# Grove_-_ADC_for_load_cell_HX711.net
KiCad netlist of a schematic drawn in EAGLE
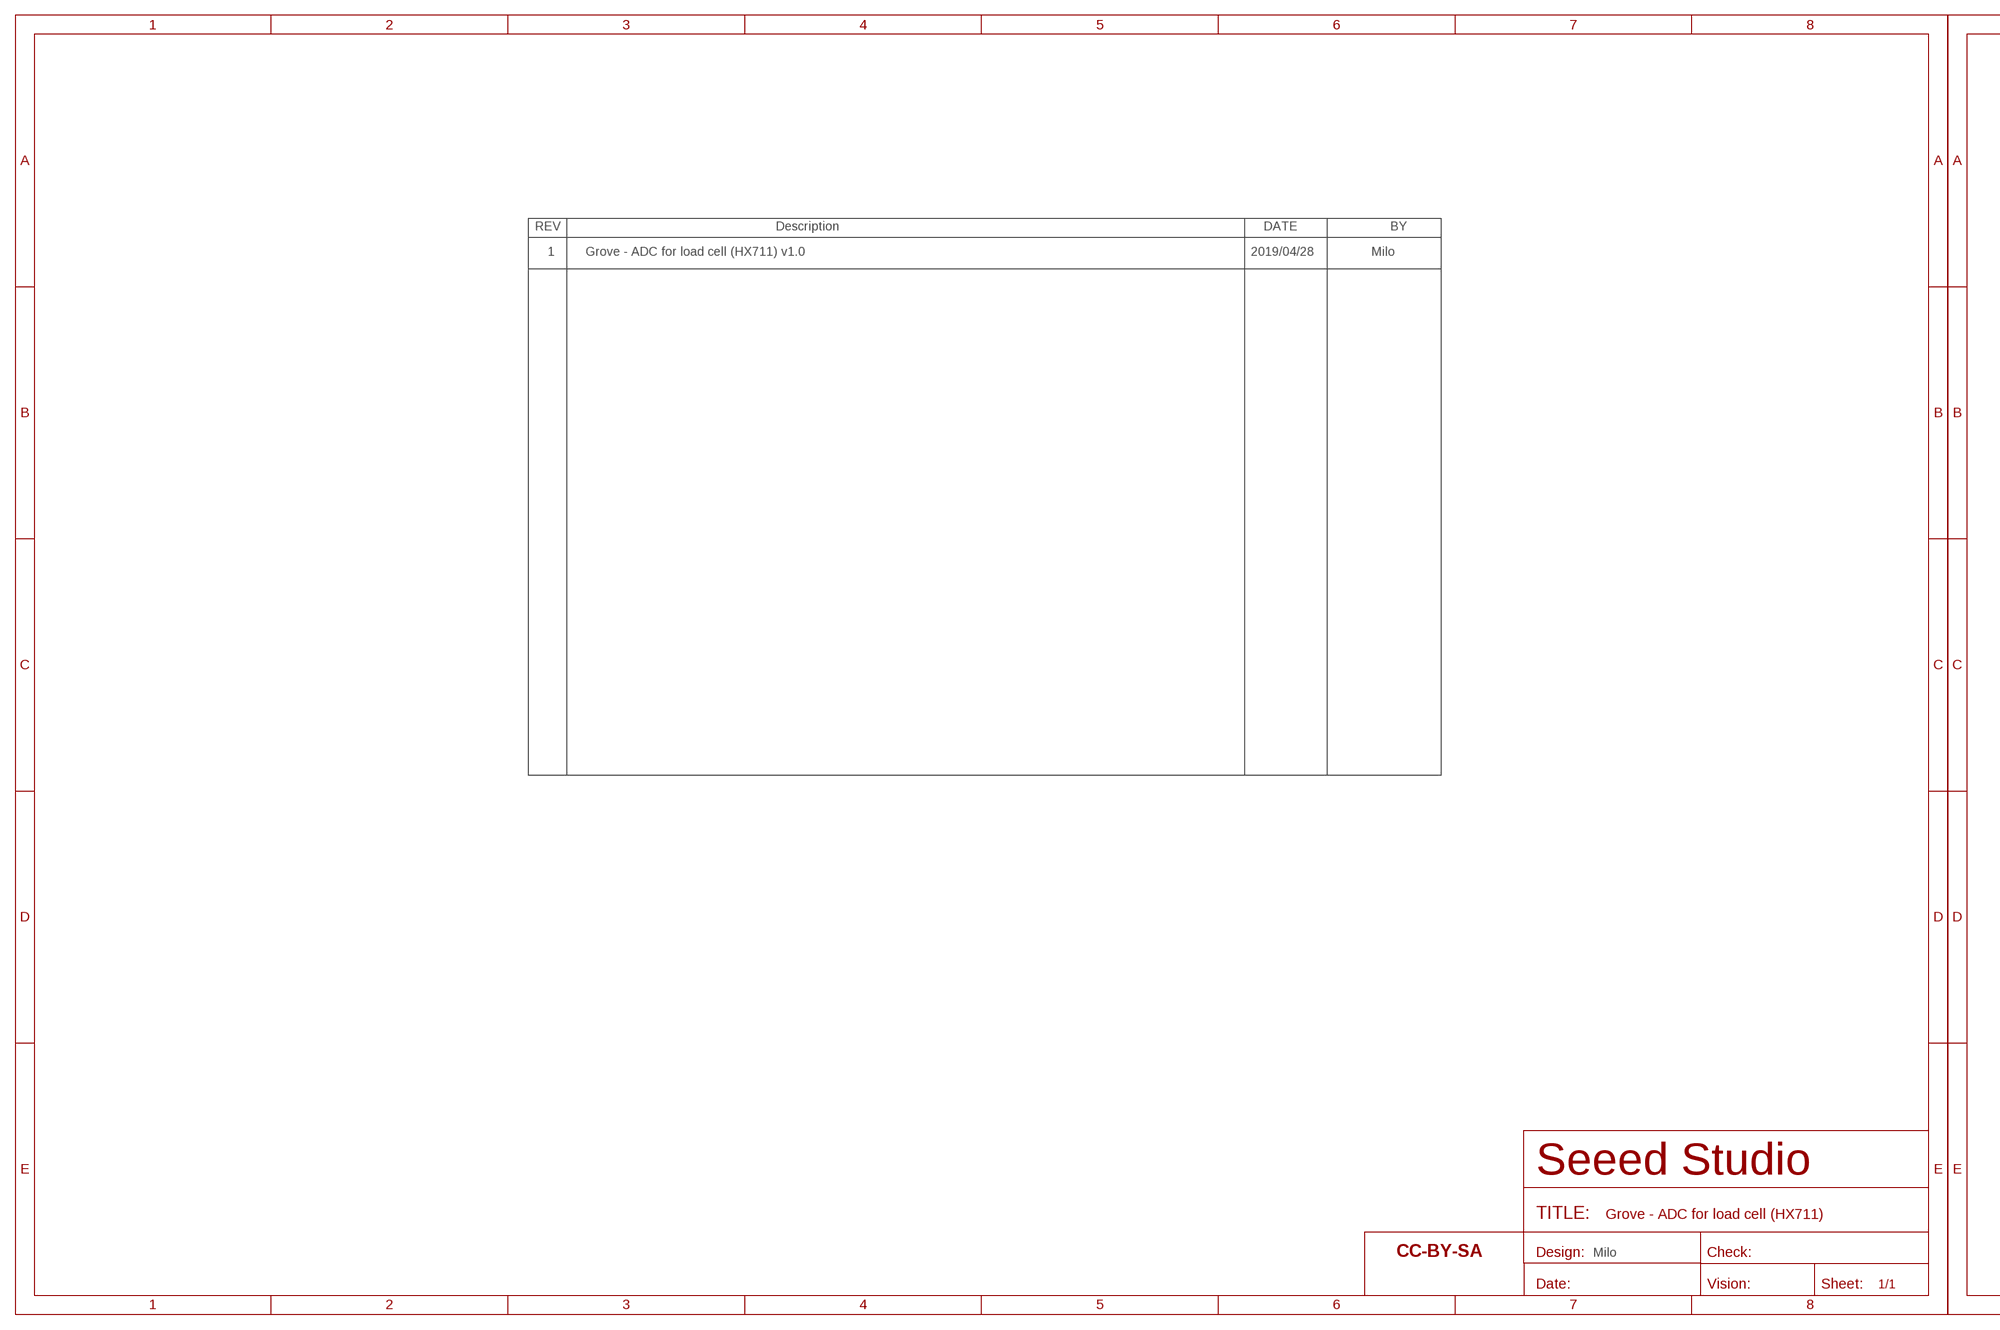
[diagram p0: schematic, sheet 1, part 1 of 2]
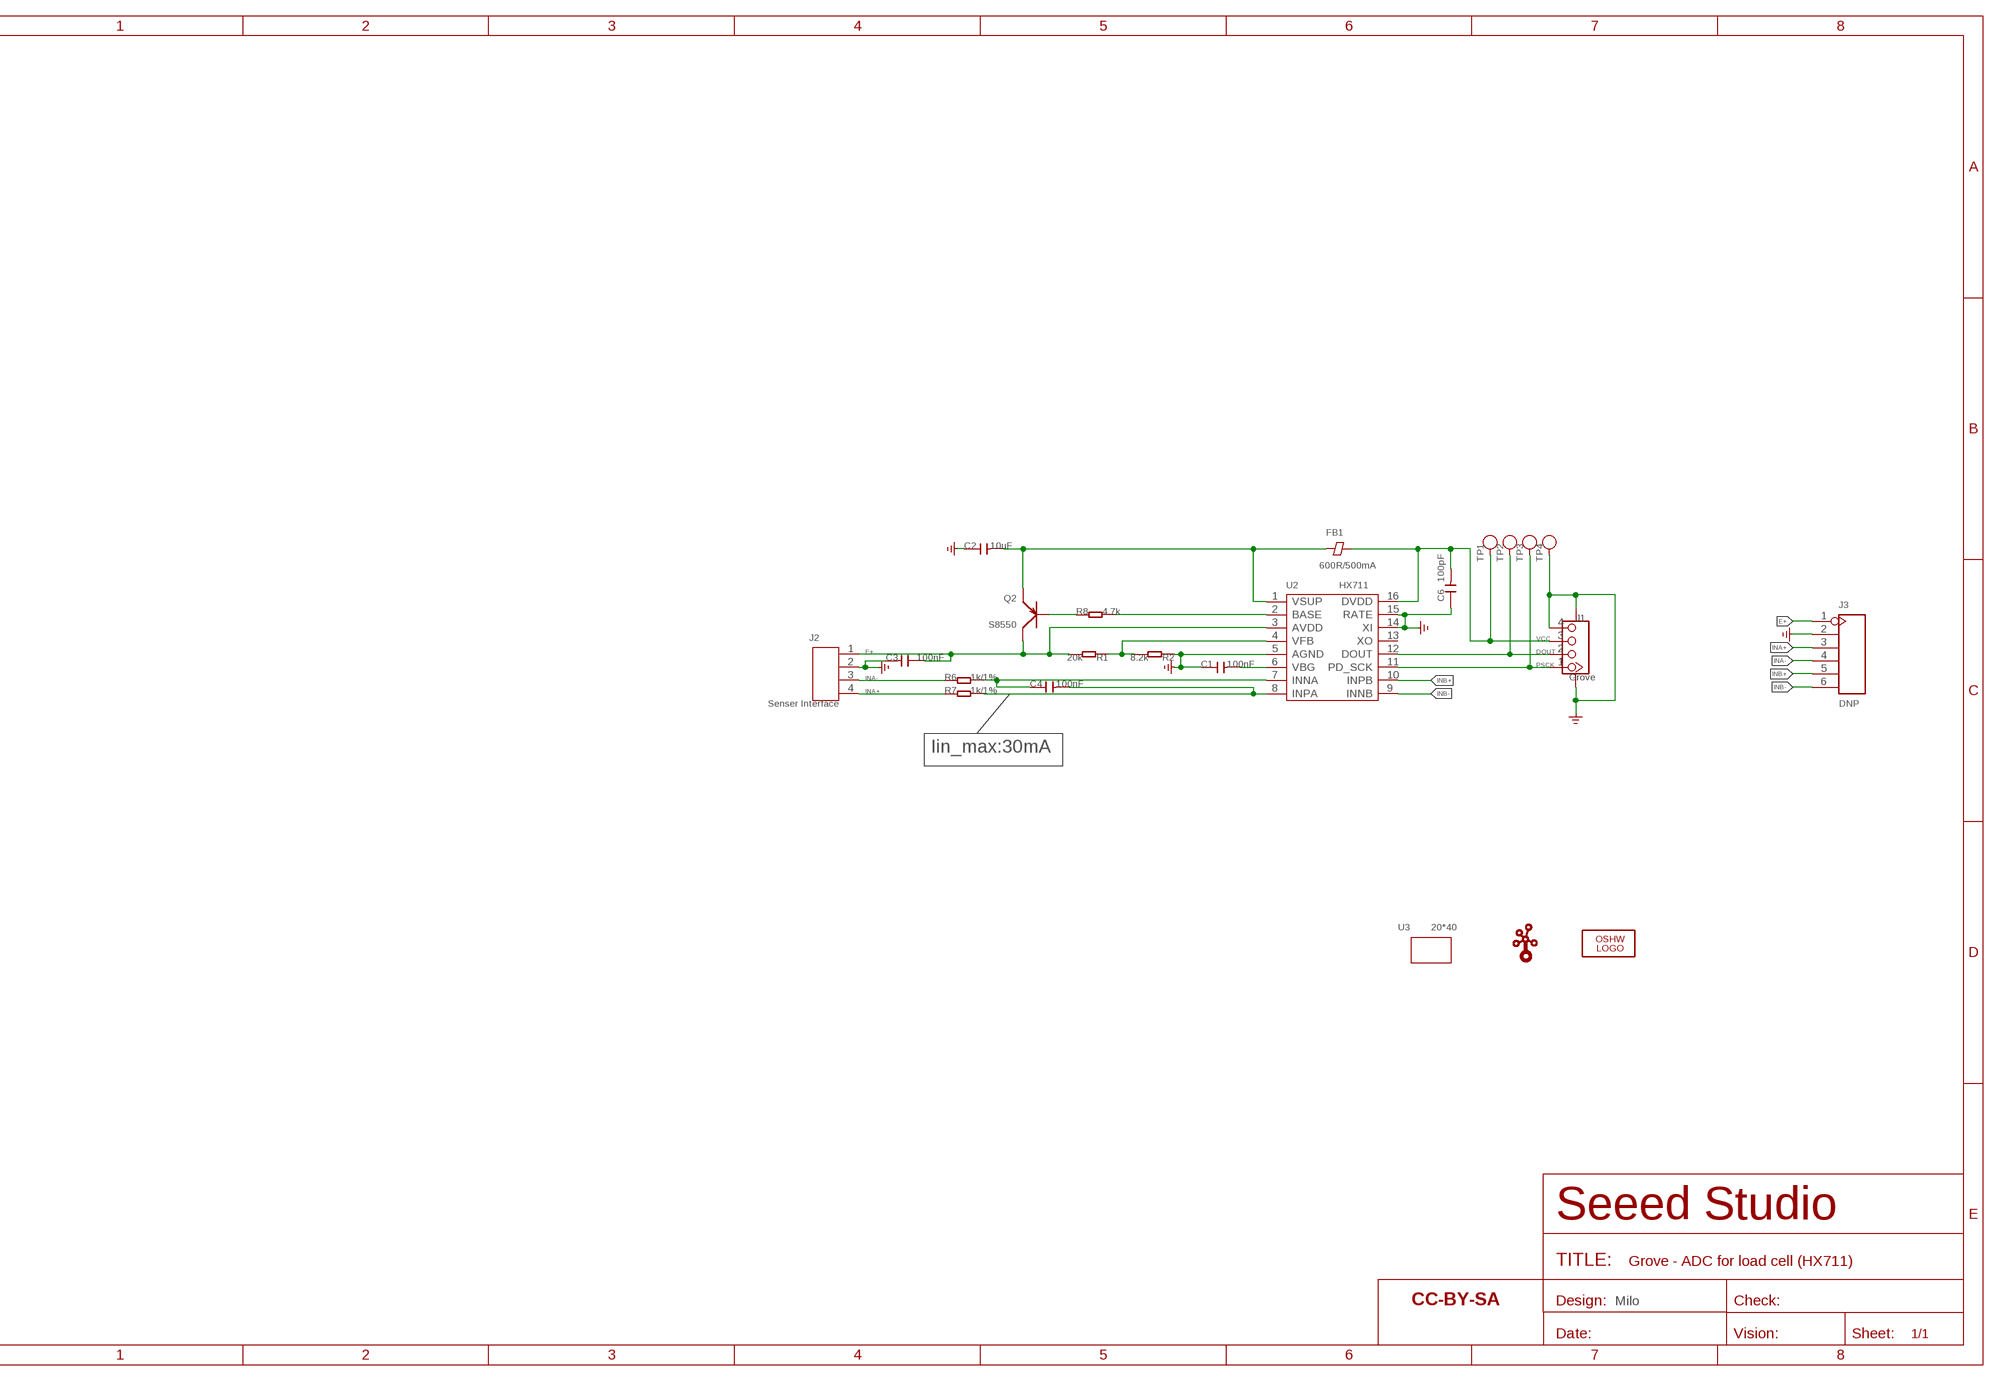
[diagram p1: schematic, sheet 1, part 2 of 2]

(export (version "E")
  (design (tool "Eeschema 10.0.6"))
  (components
    (comp (ref "C1")
      (value "100nF")
      (footprint "eagle-import:C0603")
      (libsource (lib "eagle-import") (part "CAP-0603"))
    )
    (comp (ref "C2")
      (value "10uF")
      (footprint "eagle-import:C0603")
      (libsource (lib "eagle-import") (part "CAP-0603"))
    )
    (comp (ref "C3")
      (value "100nF")
      (footprint "eagle-import:C0603")
      (libsource (lib "eagle-import") (part "CAP-0603"))
    )
    (comp (ref "C4")
      (value "100nF")
      (footprint "eagle-import:C0603")
      (libsource (lib "eagle-import") (part "CAP-0603"))
    )
    (comp (ref "C6")
      (value "100pF")
      (footprint "eagle-import:C0603")
      (libsource (lib "eagle-import") (part "CAP-0603"))
    )
    (comp (ref "FB1")
      (value "600R/500mA")
      (footprint "eagle-import:F0805")
      (libsource (lib "eagle-import") (part "FERRITE-BEAD-0805"))
    )
    (comp (ref "J1")
      (value "Grove")
      (footprint "eagle-import:HW4-SMD-2.0")
      (libsource (lib "eagle-import") (part "GROVE-CONNECTOR-SMD-320110030"))
    )
    (comp (ref "J2")
      (value "Senser Interface")
      (footprint "eagle-import:H4-3.5-14.0X7.0MM")
      (libsource (lib "eagle-import") (part "SCREW-TERMINAL-4P'3.5'"))
    )
    (comp (ref "J3")
      (value "DNP")
      (footprint "eagle-import:H6-2.54")
      (libsource (lib "eagle-import") (part "HEADER-6P-55/35MIL"))
    )
    (comp (ref "LOGO1")
      (value "LOGO-OSHW-FILLX0150-NT")
      (footprint "eagle-import:OSHW_FILLX150_NOTEXT")
      (fields (field (name "PARTNO") "DNP"))
      (libsource (lib "eagle-import") (part "LOGO-OSHW-FILLX0150-NT"))
    )
    (comp (ref "Q2")
      (value "S8550")
      (footprint "eagle-import:SOT-23")
      (libsource (lib "eagle-import") (part "TRANSISTOR-PNP-SOT23"))
    )
    (comp (ref "R1")
      (value "20k")
      (footprint "eagle-import:R0603")
      (libsource (lib "eagle-import") (part "RES-0603"))
    )
    (comp (ref "R2")
      (value "8.2k")
      (footprint "eagle-import:R0603")
      (libsource (lib "eagle-import") (part "RES-0603"))
    )
    (comp (ref "R6")
      (value "1k/1%")
      (footprint "eagle-import:R0603")
      (libsource (lib "eagle-import") (part "RES-0603"))
    )
    (comp (ref "R7")
      (value "1k/1%")
      (footprint "eagle-import:R0603")
      (libsource (lib "eagle-import") (part "RES-0603"))
    )
    (comp (ref "R8")
      (value "4.7k")
      (footprint "eagle-import:R0603")
      (libsource (lib "eagle-import") (part "RES-0603"))
    )
    (comp (ref "TP1")
      (value "DNP")
      (footprint "eagle-import:TP-D45MIL")
      (libsource (lib "eagle-import") (part "TEST-POINT'4545'"))
    )
    (comp (ref "TP2")
      (value "DNP")
      (footprint "eagle-import:TP-D45MIL")
      (libsource (lib "eagle-import") (part "TEST-POINT'4545'"))
    )
    (comp (ref "TP3")
      (value "DNP")
      (footprint "eagle-import:TP-D45MIL")
      (libsource (lib "eagle-import") (part "TEST-POINT'4545'"))
    )
    (comp (ref "TP4")
      (value "DNP")
      (footprint "eagle-import:TP-D45MIL")
      (libsource (lib "eagle-import") (part "TEST-POINT'4545'"))
    )
    (comp (ref "U$2")
      (value "LOGO-GROVE")
      (footprint "eagle-import:GROVE-SILK-BIG")
      (fields (field (name "PARTNO") "DNP"))
      (libsource (lib "eagle-import") (part "LOGO-GROVE"))
    )
    (comp (ref "U2")
      (value "HX711")
      (footprint "eagle-import:SOIC16-1.27-10X3.9MM")
      (libsource (lib "eagle-import") (part "CONVERTER-HX711"))
    )
    (comp (ref "U3")
      (value "20*40")
      (footprint "eagle-import:GROVE-1_2-TEST-PLATFORM-TOP")
      (libsource (lib "eagle-import") (part "GROVE-1X2-TOP"))
    )
  )
  (nets
    (net (code "1") (name "/DOUT") (class "Default")
      (node (ref "J1") (pin "2") (pinfunction "2_2") (pintype "bidirectional"))
      (node (ref "TP2") (pin "T") (pinfunction "T_T") (pintype "bidirectional"))
      (node (ref "U2") (pin "12") (pinfunction "DOUT_12") (pintype "bidirectional"))
    )
    (net (code "2") (name "/PSCK") (class "Default")
      (node (ref "J1") (pin "1") (pinfunction "1_1") (pintype "bidirectional"))
      (node (ref "TP3") (pin "T") (pinfunction "T_T") (pintype "bidirectional"))
      (node (ref "U2") (pin "11") (pinfunction "PD_SCK_11") (pintype "bidirectional"))
    )
    (net (code "3") (name "/VCC") (class "Default")
      (node (ref "C6") (pin "2") (pinfunction "2_2") (pintype "passive"))
      (node (ref "FB1") (pin "2") (pinfunction "2_2") (pintype "bidirectional"))
      (node (ref "J1") (pin "3") (pinfunction "3_3") (pintype "bidirectional"))
      (node (ref "TP1") (pin "T") (pinfunction "T_T") (pintype "bidirectional"))
      (node (ref "U2") (pin "16") (pinfunction "DVDD_16") (pintype "bidirectional"))
    )
    (net (code "4") (name "E+") (class "Default")
      (node (ref "C3") (pin "1") (pinfunction "1_1") (pintype "passive"))
      (node (ref "J2") (pin "1") (pinfunction "1_1") (pintype "bidirectional"))
      (node (ref "J3") (pin "1") (pinfunction "1_1") (pintype "bidirectional"))
      (node (ref "Q2") (pin "3") (pinfunction "C_3") (pintype "passive"))
      (node (ref "R1") (pin "2") (pinfunction "2_2") (pintype "passive"))
      (node (ref "U2") (pin "3") (pinfunction "AVDD_3") (pintype "bidirectional"))
    )
    (net (code "5") (name "GND_POWER") (class "Default")
      (node (ref "C1") (pin "1") (pinfunction "1_1") (pintype "passive"))
      (node (ref "C2") (pin "1") (pinfunction "1_1") (pintype "passive"))
      (node (ref "C3") (pin "2") (pinfunction "2_2") (pintype "passive"))
      (node (ref "C6") (pin "1") (pinfunction "1_1") (pintype "passive"))
      (node (ref "J1") (pin "4") (pinfunction "4_4") (pintype "bidirectional"))
      (node (ref "J1") (pin "SS1") (pinfunction "SS1_SS1") (pintype "bidirectional"))
      (node (ref "J1") (pin "SS2") (pinfunction "SS2_SS2") (pintype "bidirectional"))
      (node (ref "J2") (pin "2") (pinfunction "2_2") (pintype "bidirectional"))
      (node (ref "J3") (pin "2") (pinfunction "2_2") (pintype "bidirectional"))
      (node (ref "R2") (pin "1") (pinfunction "1_1") (pintype "passive"))
      (node (ref "TP4") (pin "T") (pinfunction "T_T") (pintype "bidirectional"))
      (node (ref "U2") (pin "14") (pinfunction "XI_14") (pintype "bidirectional"))
      (node (ref "U2") (pin "15") (pinfunction "RATE_15") (pintype "bidirectional"))
      (node (ref "U2") (pin "5") (pinfunction "AGND_5") (pintype "bidirectional"))
    )
    (net (code "6") (name "INA+") (class "Default")
      (node (ref "J2") (pin "4") (pinfunction "4_4") (pintype "bidirectional"))
      (node (ref "J3") (pin "3") (pinfunction "3_3") (pintype "bidirectional"))
      (node (ref "R7") (pin "1") (pinfunction "1_1") (pintype "passive"))
    )
    (net (code "7") (name "INA-") (class "Default")
      (node (ref "J2") (pin "3") (pinfunction "3_3") (pintype "bidirectional"))
      (node (ref "J3") (pin "4") (pinfunction "4_4") (pintype "bidirectional"))
      (node (ref "R6") (pin "1") (pinfunction "1_1") (pintype "passive"))
    )
    (net (code "8") (name "INB+") (class "Default")
      (node (ref "J3") (pin "5") (pinfunction "5_5") (pintype "bidirectional"))
      (node (ref "U2") (pin "10") (pinfunction "INPB_10") (pintype "bidirectional"))
    )
    (net (code "9") (name "INB-") (class "Default")
      (node (ref "J3") (pin "6") (pinfunction "6_6") (pintype "bidirectional"))
      (node (ref "U2") (pin "9") (pinfunction "INNB_9") (pintype "bidirectional"))
    )
    (net (code "10") (name "Net-(Q2-B)") (class "Default")
      (node (ref "Q2") (pin "1") (pinfunction "B_1") (pintype "passive"))
      (node (ref "R8") (pin "1") (pinfunction "1_1") (pintype "passive"))
    )
    (net (code "11") (name "Net-(Q2-E)") (class "Default")
      (node (ref "C2") (pin "2") (pinfunction "2_2") (pintype "passive"))
      (node (ref "FB1") (pin "1") (pinfunction "1_1") (pintype "bidirectional"))
      (node (ref "Q2") (pin "2") (pinfunction "E_2") (pintype "passive"))
      (node (ref "U2") (pin "1") (pinfunction "VSUP_1") (pintype "bidirectional"))
    )
    (net (code "12") (name "Net-(U2-BASE)") (class "Default")
      (node (ref "R8") (pin "2") (pinfunction "2_2") (pintype "passive"))
      (node (ref "U2") (pin "2") (pinfunction "BASE_2") (pintype "bidirectional"))
    )
    (net (code "13") (name "Net-(U2-INNA)") (class "Default")
      (node (ref "C4") (pin "1") (pinfunction "1_1") (pintype "passive"))
      (node (ref "R6") (pin "2") (pinfunction "2_2") (pintype "passive"))
      (node (ref "U2") (pin "7") (pinfunction "INNA_7") (pintype "bidirectional"))
    )
    (net (code "14") (name "Net-(U2-INPA)") (class "Default")
      (node (ref "C4") (pin "2") (pinfunction "2_2") (pintype "passive"))
      (node (ref "R7") (pin "2") (pinfunction "2_2") (pintype "passive"))
      (node (ref "U2") (pin "8") (pinfunction "INPA_8") (pintype "bidirectional"))
    )
    (net (code "15") (name "Net-(U2-VBG)") (class "Default")
      (node (ref "C1") (pin "2") (pinfunction "2_2") (pintype "passive"))
      (node (ref "U2") (pin "6") (pinfunction "VBG_6") (pintype "bidirectional"))
    )
    (net (code "16") (name "Net-(U2-VFB)") (class "Default")
      (node (ref "R1") (pin "1") (pinfunction "1_1") (pintype "passive"))
      (node (ref "R2") (pin "2") (pinfunction "2_2") (pintype "passive"))
      (node (ref "U2") (pin "4") (pinfunction "VFB_4") (pintype "bidirectional"))
    )
    (net (code "17") (name "unconnected-(U2-XO-Pad13)") (class "Default")
      (node (ref "U2") (pin "13") (pinfunction "XO_13") (pintype "bidirectional"))
    )
  )
)
